# arduino_shield.net
KiCad netlist of a schematic drawn in EAGLE
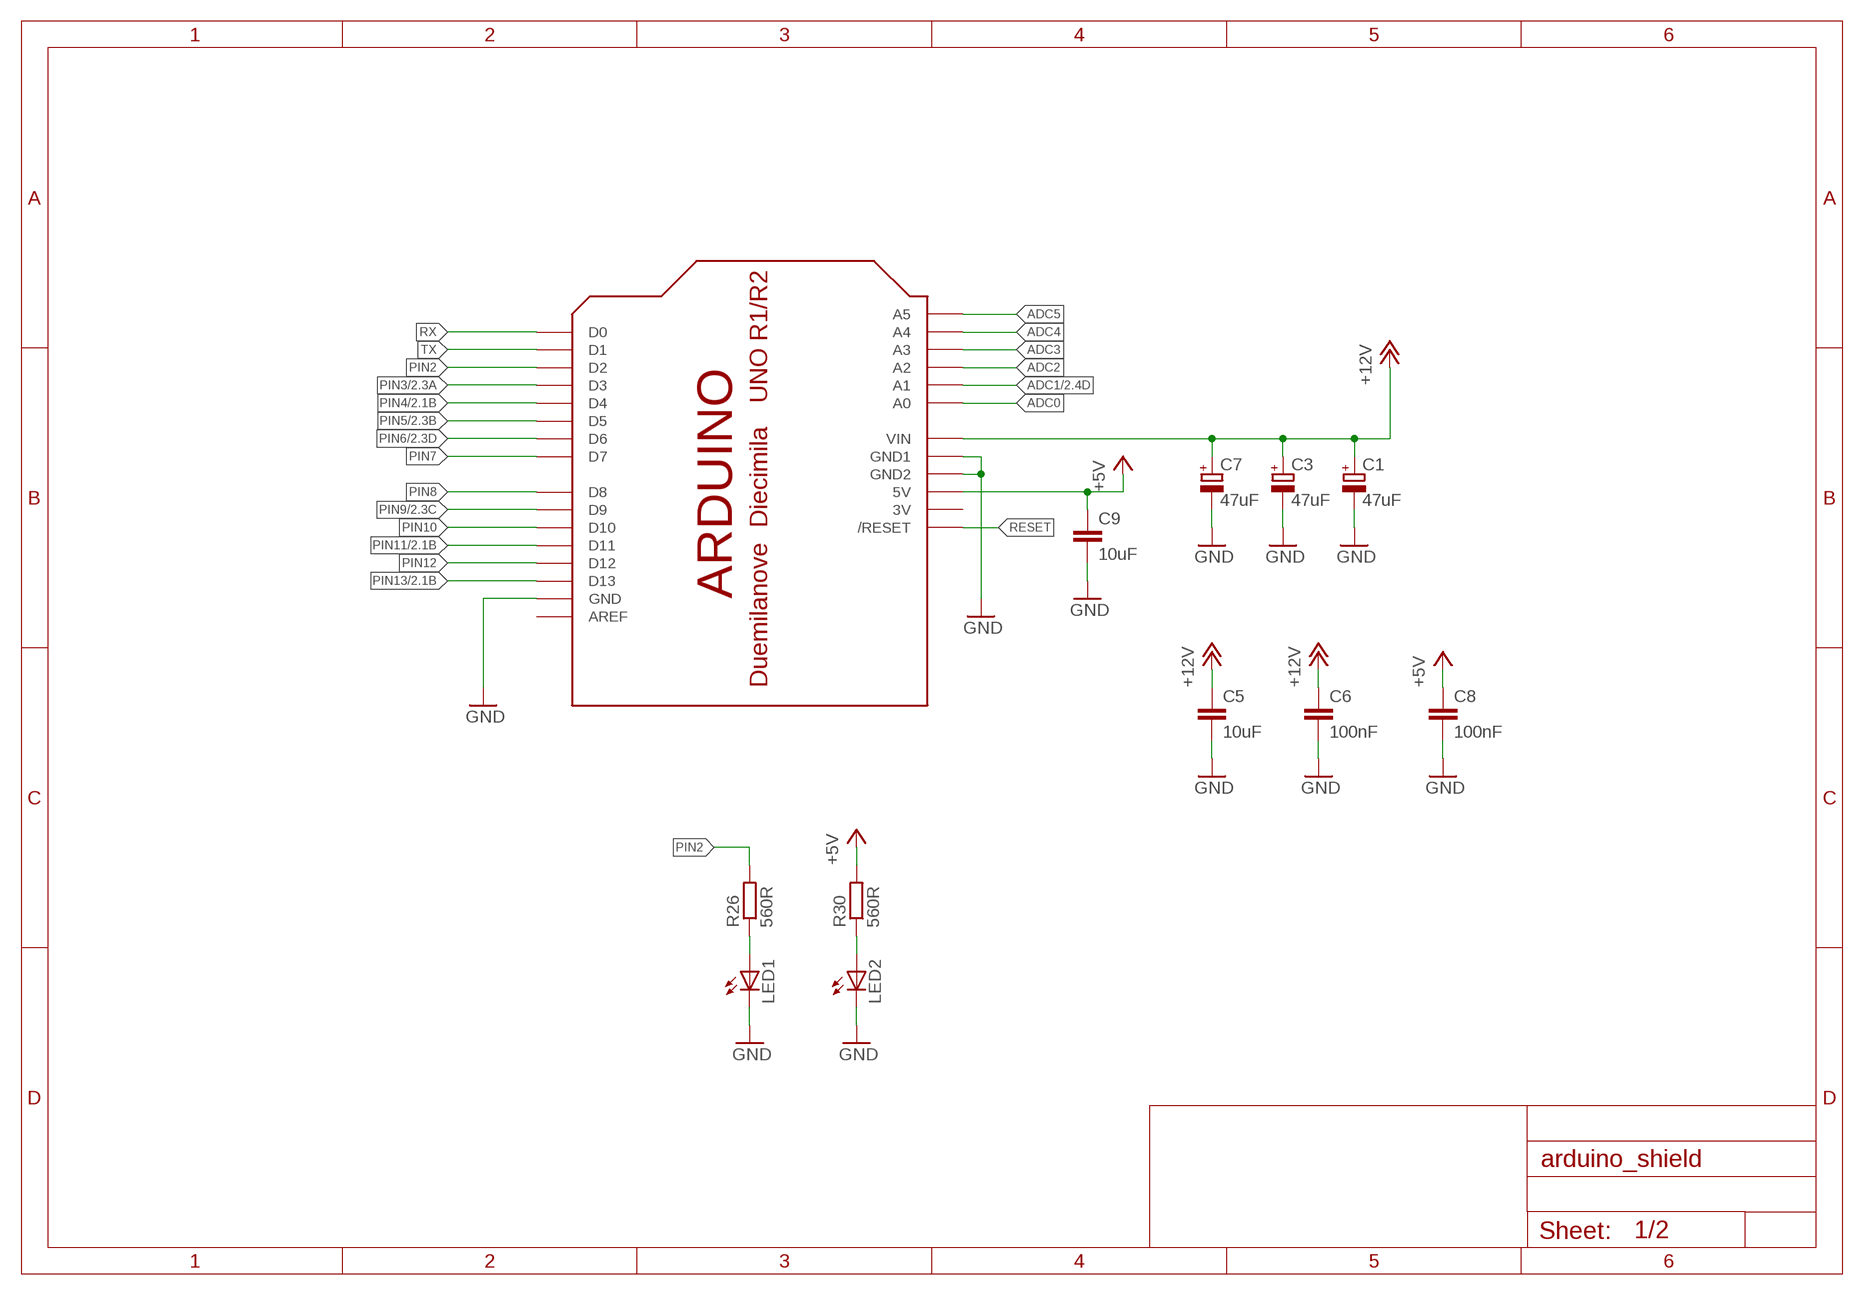
[diagram p0: schematic, sheet 1]
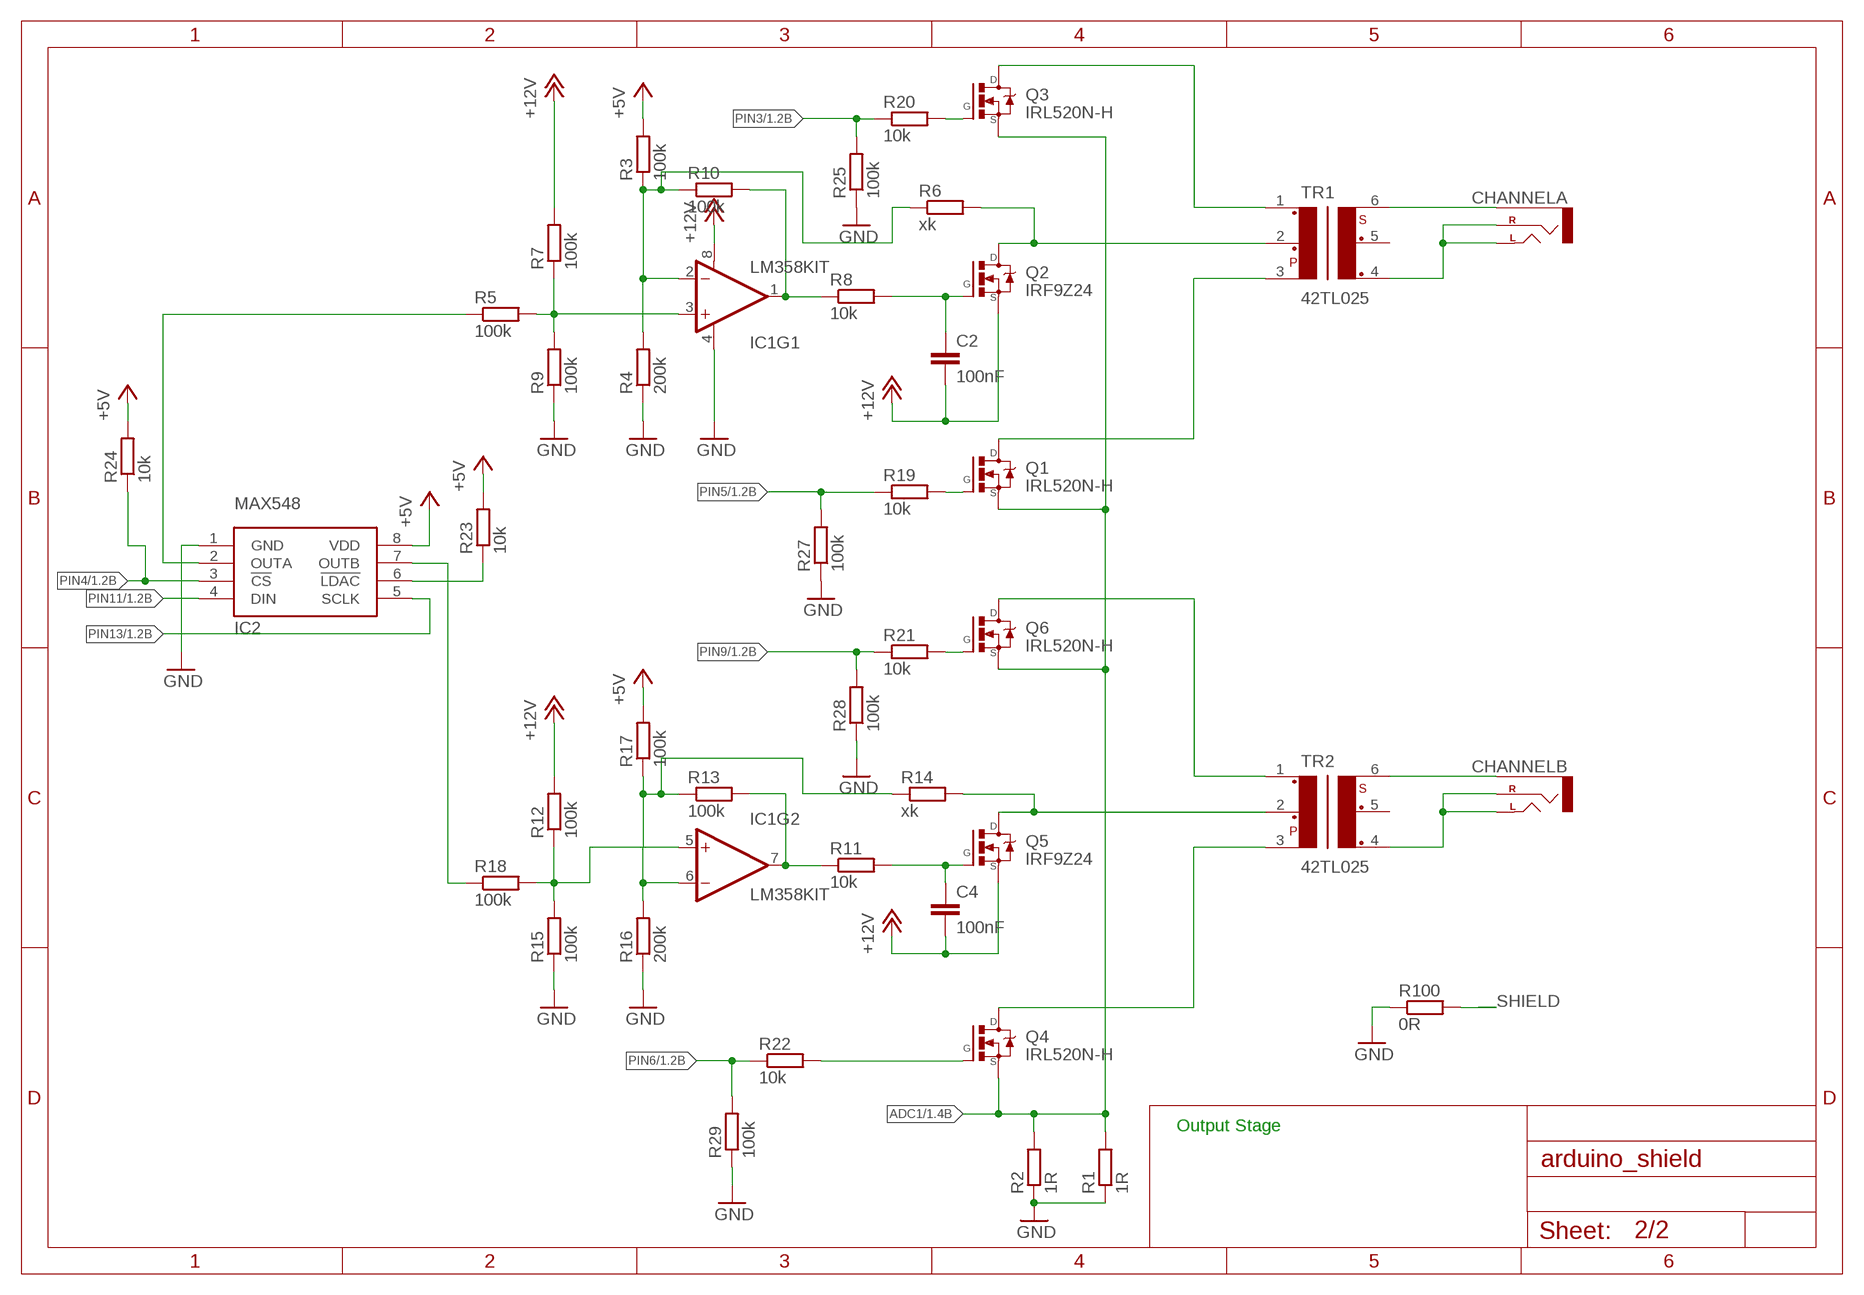
[diagram p1: schematic, sheet 2]

(export (version "E")
  (design (tool "Eeschema 10.0.6"))
  (components
    (comp (ref "C1")
      (value "47uF")
      (footprint "eagle-import:E2,5-5")
      (libsource (lib "eagle-import") (part "CPOL-EUE2.5-5"))
    )
    (comp (ref "C3")
      (value "47uF")
      (footprint "eagle-import:E2,5-5")
      (libsource (lib "eagle-import") (part "CPOL-EUE2.5-5"))
    )
    (comp (ref "C5")
      (value "10uF")
      (footprint "eagle-import:C0805K")
      (libsource (lib "eagle-import") (part "C-EUC0805K"))
    )
    (comp (ref "C6")
      (value "100nF")
      (footprint "eagle-import:C0805K")
      (libsource (lib "eagle-import") (part "C-EUC0805K"))
    )
    (comp (ref "C7")
      (value "47uF")
      (footprint "eagle-import:E2,5-5")
      (libsource (lib "eagle-import") (part "CPOL-EUE2.5-5"))
    )
    (comp (ref "C8")
      (value "100nF")
      (footprint "eagle-import:C0805K")
      (libsource (lib "eagle-import") (part "C-EUC0805K"))
    )
    (comp (ref "C9")
      (value "10uF")
      (footprint "eagle-import:C0805K")
      (libsource (lib "eagle-import") (part "C-EUC0805K"))
    )
    (comp (ref "GND")
      (value "ARDUINOUNO")
      (footprint "eagle-import:ARDUINO")
      (libsource (lib "eagle-import") (part "ARDUINOUNO"))
    )
    (comp (ref "LED1")
      (value "LEDCHIP-LED0805")
      (footprint "eagle-import:CHIP-LED0805")
      (libsource (lib "eagle-import") (part "LEDCHIP-LED0805"))
    )
    (comp (ref "LED2")
      (value "LEDCHIP-LED0805")
      (footprint "eagle-import:CHIP-LED0805")
      (libsource (lib "eagle-import") (part "LEDCHIP-LED0805"))
    )
    (comp (ref "R26")
      (value "560R")
      (footprint "eagle-import:R0805")
      (libsource (lib "eagle-import") (part "R-EU_R0805"))
    )
    (comp (ref "R30")
      (value "560R")
      (footprint "eagle-import:R0805")
      (libsource (lib "eagle-import") (part "R-EU_R0805"))
    )
    (comp (ref "C2")
      (value "100nF")
      (footprint "eagle-import:C2.5-2")
      (libsource (lib "eagle-import") (part "C2.5/2"))
    )
    (comp (ref "C4")
      (value "100nF")
      (footprint "eagle-import:C2.5-2")
      (libsource (lib "eagle-import") (part "C2.5/2"))
    )
    (comp (ref "CHANNELA")
      (value "AUDIO-JACK2.5MM")
      (footprint "eagle-import:STEREOJACK2.5MM_STEREOJACK2.5MM")
      (libsource (lib "eagle-import") (part "AUDIO-JACK2.5MM"))
    )
    (comp (ref "CHANNELB")
      (value "AUDIO-JACK2.5MM")
      (footprint "eagle-import:STEREOJACK2.5MM_STEREOJACK2.5MM")
      (libsource (lib "eagle-import") (part "AUDIO-JACK2.5MM"))
    )
    (comp (ref "IC1")
      (value "LM358KIT")
      (footprint "eagle-import:DIP08-KIT")
      (libsource (lib "eagle-import") (part "LM358KIT"))
    )
    (comp (ref "IC2")
      (value "MAX548")
      (footprint "eagle-import:DIL08")
      (libsource (lib "eagle-import") (part "MAX548"))
    )
    (comp (ref "Q1")
      (value "IRL520N-H")
      (footprint "eagle-import:TO220V")
      (libsource (lib "eagle-import") (part "IRL530N-V"))
    )
    (comp (ref "Q2")
      (value "IRF9Z24")
      (footprint "eagle-import:TO220V")
      (libsource (lib "eagle-import") (part "IRL530N-V"))
    )
    (comp (ref "Q3")
      (value "IRL520N-H")
      (footprint "eagle-import:TO220V")
      (libsource (lib "eagle-import") (part "IRL530N-V"))
    )
    (comp (ref "Q4")
      (value "IRL520N-H")
      (footprint "eagle-import:TO220V")
      (libsource (lib "eagle-import") (part "IRL530N-V"))
    )
    (comp (ref "Q5")
      (value "IRF9Z24")
      (footprint "eagle-import:TO220V")
      (libsource (lib "eagle-import") (part "IRL530N-V"))
    )
    (comp (ref "Q6")
      (value "IRL520N-H")
      (footprint "eagle-import:TO220V")
      (libsource (lib "eagle-import") (part "IRL530N-V"))
    )
    (comp (ref "R1")
      (value "1R")
      (footprint "eagle-import:R0805")
      (libsource (lib "eagle-import") (part "R"))
    )
    (comp (ref "R2")
      (value "1R")
      (footprint "eagle-import:R0805")
      (libsource (lib "eagle-import") (part "R"))
    )
    (comp (ref "R3")
      (value "100k")
      (footprint "eagle-import:R0805")
      (libsource (lib "eagle-import") (part "R"))
    )
    (comp (ref "R4")
      (value "200k")
      (footprint "eagle-import:R0805")
      (libsource (lib "eagle-import") (part "R"))
    )
    (comp (ref "R5")
      (value "100k")
      (footprint "eagle-import:R0805")
      (libsource (lib "eagle-import") (part "R"))
    )
    (comp (ref "R6")
      (value "xk")
      (footprint "eagle-import:R0805")
      (libsource (lib "eagle-import") (part "R"))
    )
    (comp (ref "R7")
      (value "100k")
      (footprint "eagle-import:R0805")
      (libsource (lib "eagle-import") (part "R"))
    )
    (comp (ref "R8")
      (value "10k")
      (footprint "eagle-import:R0805")
      (libsource (lib "eagle-import") (part "R"))
    )
    (comp (ref "R9")
      (value "100k")
      (footprint "eagle-import:R0805")
      (libsource (lib "eagle-import") (part "R"))
    )
    (comp (ref "R10")
      (value "100k")
      (footprint "eagle-import:R0805")
      (libsource (lib "eagle-import") (part "R"))
    )
    (comp (ref "R11")
      (value "10k")
      (footprint "eagle-import:R0805")
      (libsource (lib "eagle-import") (part "R"))
    )
    (comp (ref "R12")
      (value "100k")
      (footprint "eagle-import:R0805")
      (libsource (lib "eagle-import") (part "R"))
    )
    (comp (ref "R13")
      (value "100k")
      (footprint "eagle-import:R0805")
      (libsource (lib "eagle-import") (part "R"))
    )
    (comp (ref "R14")
      (value "xk")
      (footprint "eagle-import:R0805")
      (libsource (lib "eagle-import") (part "R"))
    )
    (comp (ref "R15")
      (value "100k")
      (footprint "eagle-import:R0805")
      (libsource (lib "eagle-import") (part "R"))
    )
    (comp (ref "R16")
      (value "200k")
      (footprint "eagle-import:R0805")
      (libsource (lib "eagle-import") (part "R"))
    )
    (comp (ref "R17")
      (value "100k")
      (footprint "eagle-import:R0805")
      (libsource (lib "eagle-import") (part "R"))
    )
    (comp (ref "R18")
      (value "100k")
      (footprint "eagle-import:R0805")
      (libsource (lib "eagle-import") (part "R"))
    )
    (comp (ref "R19")
      (value "10k")
      (footprint "eagle-import:R0805")
      (libsource (lib "eagle-import") (part "R"))
    )
    (comp (ref "R20")
      (value "10k")
      (footprint "eagle-import:R0805")
      (libsource (lib "eagle-import") (part "R"))
    )
    (comp (ref "R21")
      (value "10k")
      (footprint "eagle-import:R0805")
      (libsource (lib "eagle-import") (part "R"))
    )
    (comp (ref "R22")
      (value "10k")
      (footprint "eagle-import:R0805")
      (libsource (lib "eagle-import") (part "R"))
    )
    (comp (ref "R23")
      (value "10k")
      (footprint "eagle-import:R0805")
      (libsource (lib "eagle-import") (part "R"))
    )
    (comp (ref "R24")
      (value "10k")
      (footprint "eagle-import:R0805")
      (libsource (lib "eagle-import") (part "R"))
    )
    (comp (ref "R25")
      (value "100k")
      (footprint "eagle-import:R0805")
      (libsource (lib "eagle-import") (part "R"))
    )
    (comp (ref "R27")
      (value "100k")
      (footprint "eagle-import:R0805")
      (libsource (lib "eagle-import") (part "R"))
    )
    (comp (ref "R28")
      (value "100k")
      (footprint "eagle-import:R0805")
      (libsource (lib "eagle-import") (part "R"))
    )
    (comp (ref "R29")
      (value "100k")
      (footprint "eagle-import:R0805")
      (libsource (lib "eagle-import") (part "R"))
    )
    (comp (ref "R100")
      (value "0R")
      (footprint "eagle-import:R0805")
      (libsource (lib "eagle-import") (part "R"))
    )
    (comp (ref "TR1")
      (value "42TL025")
      (footprint "eagle-import:42TL")
      (libsource (lib "eagle-import") (part "42T?L025"))
    )
    (comp (ref "TR2")
      (value "42TL025")
      (footprint "eagle-import:42TL")
      (libsource (lib "eagle-import") (part "42T?L025"))
    )
  )
  (nets
    (net (code "1") (name "+5V") (class "Default")
      (node (ref "C8") (pin "1") (pinfunction "1_1") (pintype "passive"))
      (node (ref "C9") (pin "1") (pinfunction "1_1") (pintype "passive"))
      (node (ref "GND") (pin "5V") (pinfunction "5V_5V") (pintype "power_in"))
      (node (ref "IC2") (pin "8") (pinfunction "VDD_8") (pintype "bidirectional"))
      (node (ref "R17") (pin "2") (pinfunction "2_2") (pintype "passive"))
      (node (ref "R23") (pin "2") (pinfunction "2_2") (pintype "passive"))
      (node (ref "R24") (pin "2") (pinfunction "2_2") (pintype "passive"))
      (node (ref "R3") (pin "2") (pinfunction "2_2") (pintype "passive"))
      (node (ref "R30") (pin "2") (pinfunction "2_2") (pintype "passive"))
    )
    (net (code "2") (name "+12V") (class "Default")
      (node (ref "C1") (pin "+") (pinfunction "+_+") (pintype "passive"))
      (node (ref "C2") (pin "2") (pinfunction "2_2") (pintype "passive"))
      (node (ref "C3") (pin "+") (pinfunction "+_+") (pintype "passive"))
      (node (ref "C4") (pin "2") (pinfunction "2_2") (pintype "passive"))
      (node (ref "C5") (pin "1") (pinfunction "1_1") (pintype "passive"))
      (node (ref "C6") (pin "1") (pinfunction "1_1") (pintype "passive"))
      (node (ref "C7") (pin "+") (pinfunction "+_+") (pintype "passive"))
      (node (ref "GND") (pin "VIN") (pinfunction "VIN_VIN") (pintype "power_in"))
      (node (ref "IC1") (pin "8") (pinfunction "V+_8") (pintype "power_in"))
      (node (ref "Q2") (pin "3") (pinfunction "S_3") (pintype "passive"))
      (node (ref "Q5") (pin "3") (pinfunction "S_3") (pintype "passive"))
      (node (ref "R12") (pin "2") (pinfunction "2_2") (pintype "passive"))
      (node (ref "R7") (pin "2") (pinfunction "2_2") (pintype "passive"))
    )
    (net (code "3") (name "3V") (class "Default")
      (node (ref "GND") (pin "3V") (pinfunction "3V_3V") (pintype "power_in"))
    )
    (net (code "4") (name "ADC0") (class "Default")
      (node (ref "GND") (pin "A0") (pinfunction "A0_A0") (pintype "bidirectional"))
    )
    (net (code "5") (name "ADC1") (class "Default")
      (node (ref "GND") (pin "A1") (pinfunction "A1_A1") (pintype "bidirectional"))
      (node (ref "Q1") (pin "3") (pinfunction "S_3") (pintype "passive"))
      (node (ref "Q3") (pin "3") (pinfunction "S_3") (pintype "passive"))
      (node (ref "Q4") (pin "3") (pinfunction "S_3") (pintype "passive"))
      (node (ref "Q6") (pin "3") (pinfunction "S_3") (pintype "passive"))
      (node (ref "R1") (pin "2") (pinfunction "2_2") (pintype "passive"))
      (node (ref "R2") (pin "2") (pinfunction "2_2") (pintype "passive"))
    )
    (net (code "6") (name "ADC2") (class "Default")
      (node (ref "GND") (pin "A2") (pinfunction "A2_A2") (pintype "bidirectional"))
    )
    (net (code "7") (name "ADC3") (class "Default")
      (node (ref "GND") (pin "A3") (pinfunction "A3_A3") (pintype "bidirectional"))
    )
    (net (code "8") (name "ADC4") (class "Default")
      (node (ref "GND") (pin "A4") (pinfunction "A4_A4") (pintype "bidirectional"))
    )
    (net (code "9") (name "ADC5") (class "Default")
      (node (ref "GND") (pin "A5") (pinfunction "A5_A5") (pintype "bidirectional"))
    )
    (net (code "10") (name "GND") (class "Default")
      (node (ref "C1") (pin "-") (pinfunction "-_-") (pintype "passive"))
      (node (ref "C3") (pin "-") (pinfunction "-_-") (pintype "passive"))
      (node (ref "C5") (pin "2") (pinfunction "2_2") (pintype "passive"))
      (node (ref "C6") (pin "2") (pinfunction "2_2") (pintype "passive"))
      (node (ref "C7") (pin "-") (pinfunction "-_-") (pintype "passive"))
      (node (ref "C8") (pin "2") (pinfunction "2_2") (pintype "passive"))
      (node (ref "C9") (pin "2") (pinfunction "2_2") (pintype "passive"))
      (node (ref "GND") (pin "GND") (pinfunction "GND_GND") (pintype "power_in"))
      (node (ref "GND") (pin "GND1") (pinfunction "GND1_GND1") (pintype "power_in"))
      (node (ref "GND") (pin "GND2") (pinfunction "GND2_GND2") (pintype "power_in"))
      (node (ref "IC1") (pin "4") (pinfunction "V-_4") (pintype "power_in"))
      (node (ref "IC2") (pin "1") (pinfunction "GND_1") (pintype "bidirectional"))
      (node (ref "LED1") (pin "C") (pinfunction "C_C") (pintype "passive"))
      (node (ref "LED2") (pin "C") (pinfunction "C_C") (pintype "passive"))
      (node (ref "R1") (pin "1") (pinfunction "1_1") (pintype "passive"))
      (node (ref "R100") (pin "1") (pinfunction "1_1") (pintype "passive"))
      (node (ref "R15") (pin "1") (pinfunction "1_1") (pintype "passive"))
      (node (ref "R16") (pin "1") (pinfunction "1_1") (pintype "passive"))
      (node (ref "R2") (pin "1") (pinfunction "1_1") (pintype "passive"))
      (node (ref "R25") (pin "1") (pinfunction "1_1") (pintype "passive"))
      (node (ref "R27") (pin "1") (pinfunction "1_1") (pintype "passive"))
      (node (ref "R28") (pin "1") (pinfunction "1_1") (pintype "passive"))
      (node (ref "R29") (pin "1") (pinfunction "1_1") (pintype "passive"))
      (node (ref "R4") (pin "1") (pinfunction "1_1") (pintype "passive"))
      (node (ref "R9") (pin "1") (pinfunction "1_1") (pintype "passive"))
    )
    (net (code "11") (name "Net-(CHANNELA-LEFT)") (class "Default")
      (node (ref "CHANNELA") (pin "SHIELD") (pinfunction "LEFT_SHIELD") (pintype "bidirectional"))
      (node (ref "CHANNELA") (pin "TIP") (pinfunction "RIGHT_TIP") (pintype "bidirectional"))
      (node (ref "TR1") (pin "4") (pinfunction "4_4") (pintype "passive"))
    )
    (net (code "12") (name "Net-(CHANNELA-SLEEVE)") (class "Default")
      (node (ref "CHANNELA") (pin "RING1") (pinfunction "SLEEVE_RING1") (pintype "bidirectional"))
      (node (ref "TR1") (pin "6") (pinfunction "6_6") (pintype "passive"))
    )
    (net (code "13") (name "Net-(CHANNELB-LEFT)") (class "Default")
      (node (ref "CHANNELB") (pin "SHIELD") (pinfunction "LEFT_SHIELD") (pintype "bidirectional"))
      (node (ref "CHANNELB") (pin "TIP") (pinfunction "RIGHT_TIP") (pintype "bidirectional"))
      (node (ref "TR2") (pin "4") (pinfunction "4_4") (pintype "passive"))
    )
    (net (code "14") (name "Net-(CHANNELB-SLEEVE)") (class "Default")
      (node (ref "CHANNELB") (pin "RING1") (pinfunction "SLEEVE_RING1") (pintype "bidirectional"))
      (node (ref "TR2") (pin "6") (pinfunction "6_6") (pintype "passive"))
    )
    (net (code "15") (name "Net-(IC1A-+IN)") (class "Default")
      (node (ref "IC1") (pin "3") (pinfunction "+IN_3") (pintype "input"))
      (node (ref "R5") (pin "2") (pinfunction "2_2") (pintype "passive"))
      (node (ref "R7") (pin "1") (pinfunction "1_1") (pintype "passive"))
      (node (ref "R9") (pin "2") (pinfunction "2_2") (pintype "passive"))
    )
    (net (code "16") (name "Net-(IC1A--IN)") (class "Default")
      (node (ref "IC1") (pin "2") (pinfunction "-IN_2") (pintype "input"))
      (node (ref "R10") (pin "1") (pinfunction "1_1") (pintype "passive"))
      (node (ref "R3") (pin "1") (pinfunction "1_1") (pintype "passive"))
      (node (ref "R4") (pin "2") (pinfunction "2_2") (pintype "passive"))
      (node (ref "R6") (pin "1") (pinfunction "1_1") (pintype "passive"))
    )
    (net (code "17") (name "Net-(IC1A-OUT)") (class "Default")
      (node (ref "IC1") (pin "1") (pinfunction "OUT_1") (pintype "output"))
      (node (ref "R10") (pin "2") (pinfunction "2_2") (pintype "passive"))
      (node (ref "R8") (pin "1") (pinfunction "1_1") (pintype "passive"))
    )
    (net (code "18") (name "Net-(IC1B-+IN)") (class "Default")
      (node (ref "IC1") (pin "5") (pinfunction "+IN_5") (pintype "input"))
      (node (ref "R12") (pin "1") (pinfunction "1_1") (pintype "passive"))
      (node (ref "R15") (pin "2") (pinfunction "2_2") (pintype "passive"))
      (node (ref "R18") (pin "2") (pinfunction "2_2") (pintype "passive"))
    )
    (net (code "19") (name "Net-(IC1B--IN)") (class "Default")
      (node (ref "IC1") (pin "6") (pinfunction "-IN_6") (pintype "input"))
      (node (ref "R13") (pin "1") (pinfunction "1_1") (pintype "passive"))
      (node (ref "R14") (pin "1") (pinfunction "1_1") (pintype "passive"))
      (node (ref "R16") (pin "2") (pinfunction "2_2") (pintype "passive"))
      (node (ref "R17") (pin "1") (pinfunction "1_1") (pintype "passive"))
    )
    (net (code "20") (name "Net-(IC1B-OUT)") (class "Default")
      (node (ref "IC1") (pin "7") (pinfunction "OUT_7") (pintype "output"))
      (node (ref "R11") (pin "1") (pinfunction "1_1") (pintype "passive"))
      (node (ref "R13") (pin "2") (pinfunction "2_2") (pintype "passive"))
    )
    (net (code "21") (name "Net-(IC2-OUTA)") (class "Default")
      (node (ref "IC2") (pin "2") (pinfunction "OUTA_2") (pintype "bidirectional"))
      (node (ref "R5") (pin "1") (pinfunction "1_1") (pintype "passive"))
    )
    (net (code "22") (name "Net-(IC2-OUTB)") (class "Default")
      (node (ref "IC2") (pin "7") (pinfunction "OUTB_7") (pintype "bidirectional"))
      (node (ref "R18") (pin "1") (pinfunction "1_1") (pintype "passive"))
    )
    (net (code "23") (name "Net-(IC2-~{LDAC})") (class "Default")
      (node (ref "IC2") (pin "6") (pinfunction "~{LDAC}_6") (pintype "bidirectional"))
      (node (ref "R23") (pin "1") (pinfunction "1_1") (pintype "passive"))
    )
    (net (code "24") (name "Net-(LED1-PadA)") (class "Default")
      (node (ref "LED1") (pin "A") (pinfunction "A_A") (pintype "passive"))
      (node (ref "R26") (pin "1") (pinfunction "1_1") (pintype "passive"))
    )
    (net (code "25") (name "Net-(LED2-PadA)") (class "Default")
      (node (ref "LED2") (pin "A") (pinfunction "A_A") (pintype "passive"))
      (node (ref "R30") (pin "1") (pinfunction "1_1") (pintype "passive"))
    )
    (net (code "26") (name "Net-(Q1-D)") (class "Default")
      (node (ref "Q1") (pin "2") (pinfunction "D_2") (pintype "passive"))
      (node (ref "TR1") (pin "3") (pinfunction "3_3") (pintype "passive"))
    )
    (net (code "27") (name "Net-(Q1-G)") (class "Default")
      (node (ref "Q1") (pin "1") (pinfunction "G_1") (pintype "passive"))
      (node (ref "R19") (pin "2") (pinfunction "2_2") (pintype "passive"))
    )
    (net (code "28") (name "Net-(Q2-D)") (class "Default")
      (node (ref "Q2") (pin "2") (pinfunction "D_2") (pintype "passive"))
      (node (ref "R6") (pin "2") (pinfunction "2_2") (pintype "passive"))
      (node (ref "TR1") (pin "2") (pinfunction "2_2") (pintype "passive"))
    )
    (net (code "29") (name "Net-(Q2-G)") (class "Default")
      (node (ref "C2") (pin "1") (pinfunction "1_1") (pintype "passive"))
      (node (ref "Q2") (pin "1") (pinfunction "G_1") (pintype "passive"))
      (node (ref "R8") (pin "2") (pinfunction "2_2") (pintype "passive"))
    )
    (net (code "30") (name "Net-(Q3-D)") (class "Default")
      (node (ref "Q3") (pin "2") (pinfunction "D_2") (pintype "passive"))
      (node (ref "TR1") (pin "1") (pinfunction "1_1") (pintype "passive"))
    )
    (net (code "31") (name "Net-(Q3-G)") (class "Default")
      (node (ref "Q3") (pin "1") (pinfunction "G_1") (pintype "passive"))
      (node (ref "R20") (pin "2") (pinfunction "2_2") (pintype "passive"))
    )
    (net (code "32") (name "Net-(Q4-D)") (class "Default")
      (node (ref "Q4") (pin "2") (pinfunction "D_2") (pintype "passive"))
      (node (ref "TR2") (pin "3") (pinfunction "3_3") (pintype "passive"))
    )
    (net (code "33") (name "Net-(Q4-G)") (class "Default")
      (node (ref "Q4") (pin "1") (pinfunction "G_1") (pintype "passive"))
      (node (ref "R22") (pin "2") (pinfunction "2_2") (pintype "passive"))
    )
    (net (code "34") (name "Net-(Q5-D)") (class "Default")
      (node (ref "Q5") (pin "2") (pinfunction "D_2") (pintype "passive"))
      (node (ref "R14") (pin "2") (pinfunction "2_2") (pintype "passive"))
      (node (ref "TR2") (pin "2") (pinfunction "2_2") (pintype "passive"))
    )
    (net (code "35") (name "Net-(Q5-G)") (class "Default")
      (node (ref "C4") (pin "1") (pinfunction "1_1") (pintype "passive"))
      (node (ref "Q5") (pin "1") (pinfunction "G_1") (pintype "passive"))
      (node (ref "R11") (pin "2") (pinfunction "2_2") (pintype "passive"))
    )
    (net (code "36") (name "Net-(Q6-D)") (class "Default")
      (node (ref "Q6") (pin "2") (pinfunction "D_2") (pintype "passive"))
      (node (ref "TR2") (pin "1") (pinfunction "1_1") (pintype "passive"))
    )
    (net (code "37") (name "Net-(Q6-G)") (class "Default")
      (node (ref "Q6") (pin "1") (pinfunction "G_1") (pintype "passive"))
      (node (ref "R21") (pin "2") (pinfunction "2_2") (pintype "passive"))
    )
    (net (code "38") (name "PIN2") (class "Default")
      (node (ref "GND") (pin "D2") (pinfunction "D2_D2") (pintype "bidirectional"))
      (node (ref "R26") (pin "2") (pinfunction "2_2") (pintype "passive"))
    )
    (net (code "39") (name "PIN3") (class "Default")
      (node (ref "GND") (pin "D3") (pinfunction "D3_D3") (pintype "bidirectional"))
      (node (ref "R20") (pin "1") (pinfunction "1_1") (pintype "passive"))
      (node (ref "R25") (pin "2") (pinfunction "2_2") (pintype "passive"))
    )
    (net (code "40") (name "PIN4") (class "Default")
      (node (ref "GND") (pin "D4") (pinfunction "D4_D4") (pintype "bidirectional"))
      (node (ref "IC2") (pin "3") (pinfunction "~{CS}_3") (pintype "bidirectional"))
      (node (ref "R24") (pin "1") (pinfunction "1_1") (pintype "passive"))
    )
    (net (code "41") (name "PIN5") (class "Default")
      (node (ref "GND") (pin "D5") (pinfunction "D5_D5") (pintype "bidirectional"))
      (node (ref "R19") (pin "1") (pinfunction "1_1") (pintype "passive"))
      (node (ref "R27") (pin "2") (pinfunction "2_2") (pintype "passive"))
    )
    (net (code "42") (name "PIN6") (class "Default")
      (node (ref "GND") (pin "D6") (pinfunction "D6_D6") (pintype "bidirectional"))
      (node (ref "R22") (pin "1") (pinfunction "1_1") (pintype "passive"))
      (node (ref "R29") (pin "2") (pinfunction "2_2") (pintype "passive"))
    )
    (net (code "43") (name "PIN7") (class "Default")
      (node (ref "GND") (pin "D7") (pinfunction "D7_D7") (pintype "bidirectional"))
    )
    (net (code "44") (name "PIN8") (class "Default")
      (node (ref "GND") (pin "D8") (pinfunction "D8_D8") (pintype "bidirectional"))
    )
    (net (code "45") (name "PIN9") (class "Default")
      (node (ref "GND") (pin "D9") (pinfunction "D9_D9") (pintype "bidirectional"))
      (node (ref "R21") (pin "1") (pinfunction "1_1") (pintype "passive"))
      (node (ref "R28") (pin "2") (pinfunction "2_2") (pintype "passive"))
    )
    (net (code "46") (name "PIN10") (class "Default")
      (node (ref "GND") (pin "D10") (pinfunction "D10_D10") (pintype "bidirectional"))
    )
    (net (code "47") (name "PIN11") (class "Default")
      (node (ref "GND") (pin "D11") (pinfunction "D11_D11") (pintype "bidirectional"))
      (node (ref "IC2") (pin "4") (pinfunction "DIN_4") (pintype "bidirectional"))
    )
    (net (code "48") (name "PIN12") (class "Default")
      (node (ref "GND") (pin "D12") (pinfunction "D12_D12") (pintype "bidirectional"))
    )
    (net (code "49") (name "PIN13") (class "Default")
      (node (ref "GND") (pin "D13") (pinfunction "D13_D13") (pintype "bidirectional"))
      (node (ref "IC2") (pin "5") (pinfunction "SCLK_5") (pintype "bidirectional"))
    )
    (net (code "50") (name "RESET") (class "Default")
      (node (ref "GND") (pin "RESET") (pinfunction "/RESET_RESET") (pintype "bidirectional"))
    )
    (net (code "51") (name "RX") (class "Default")
      (node (ref "GND") (pin "D0") (pinfunction "D0_D0") (pintype "bidirectional"))
    )
    (net (code "52") (name "SHIELD") (class "Default")
      (node (ref "R100") (pin "2") (pinfunction "2_2") (pintype "passive"))
    )
    (net (code "53") (name "TX") (class "Default")
      (node (ref "GND") (pin "D1") (pinfunction "D1_D1") (pintype "bidirectional"))
    )
    (net (code "54") (name "unconnected-(GND-PadAREF)") (class "Default")
      (node (ref "GND") (pin "AREF") (pinfunction "AREF_AREF") (pintype "bidirectional"))
    )
    (net (code "55") (name "unconnected-(TR1-Pad5)") (class "Default")
      (node (ref "TR1") (pin "5") (pinfunction "5_5") (pintype "passive"))
    )
    (net (code "56") (name "unconnected-(TR2-Pad5)") (class "Default")
      (node (ref "TR2") (pin "5") (pinfunction "5_5") (pintype "passive"))
    )
  )
)
